# mano_rev_1_2_a.net
KiCad netlist of a schematic drawn in EAGLE
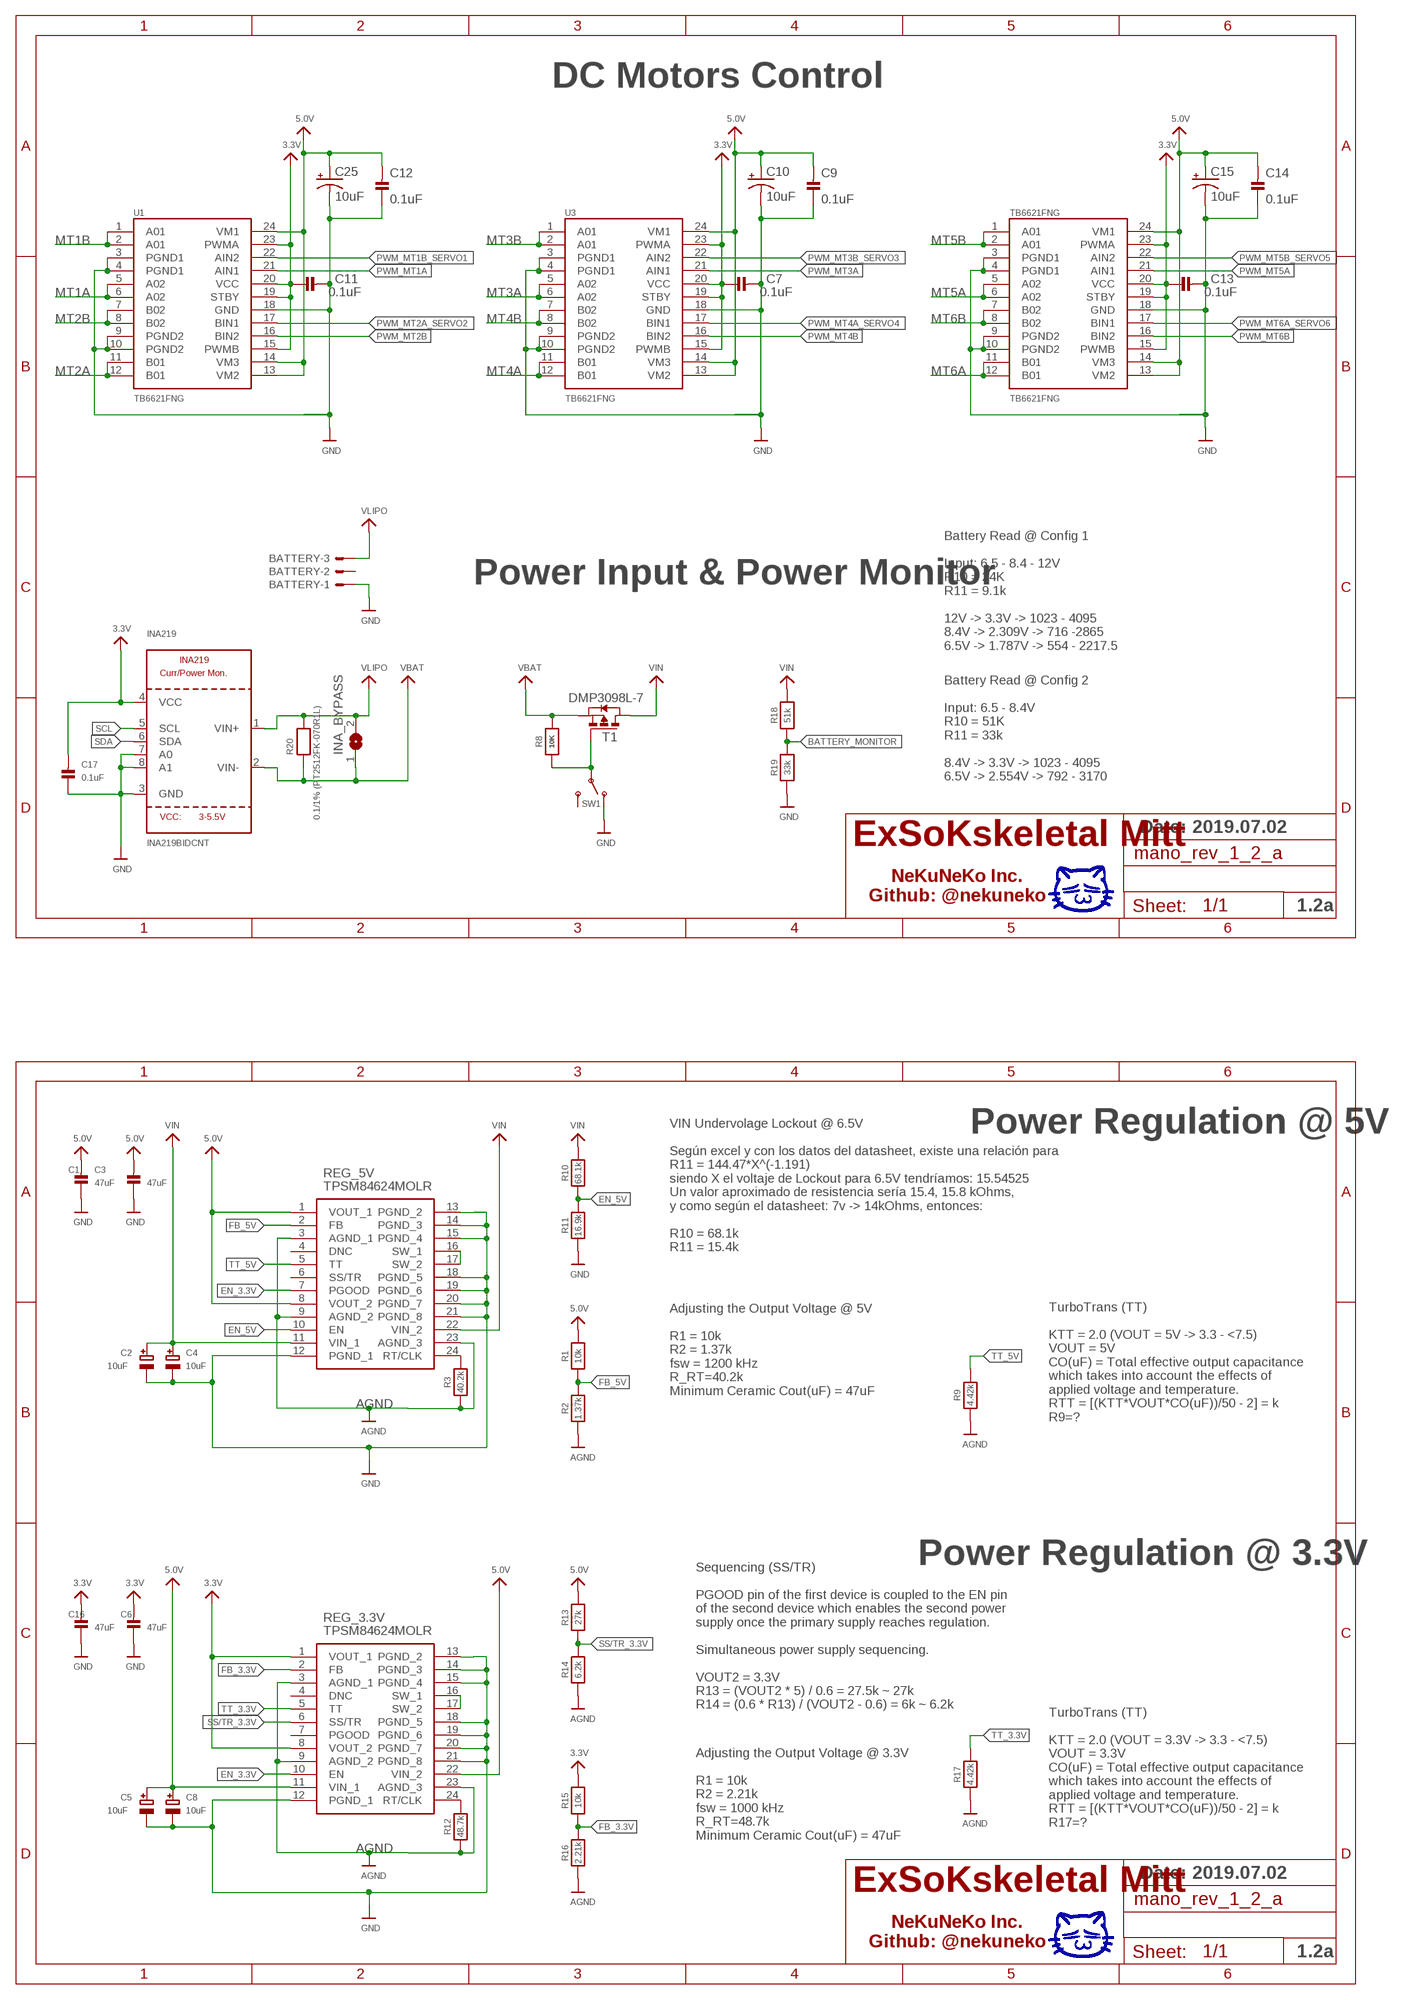
[diagram p0: schematic, sheet 1, part 1 of 2]
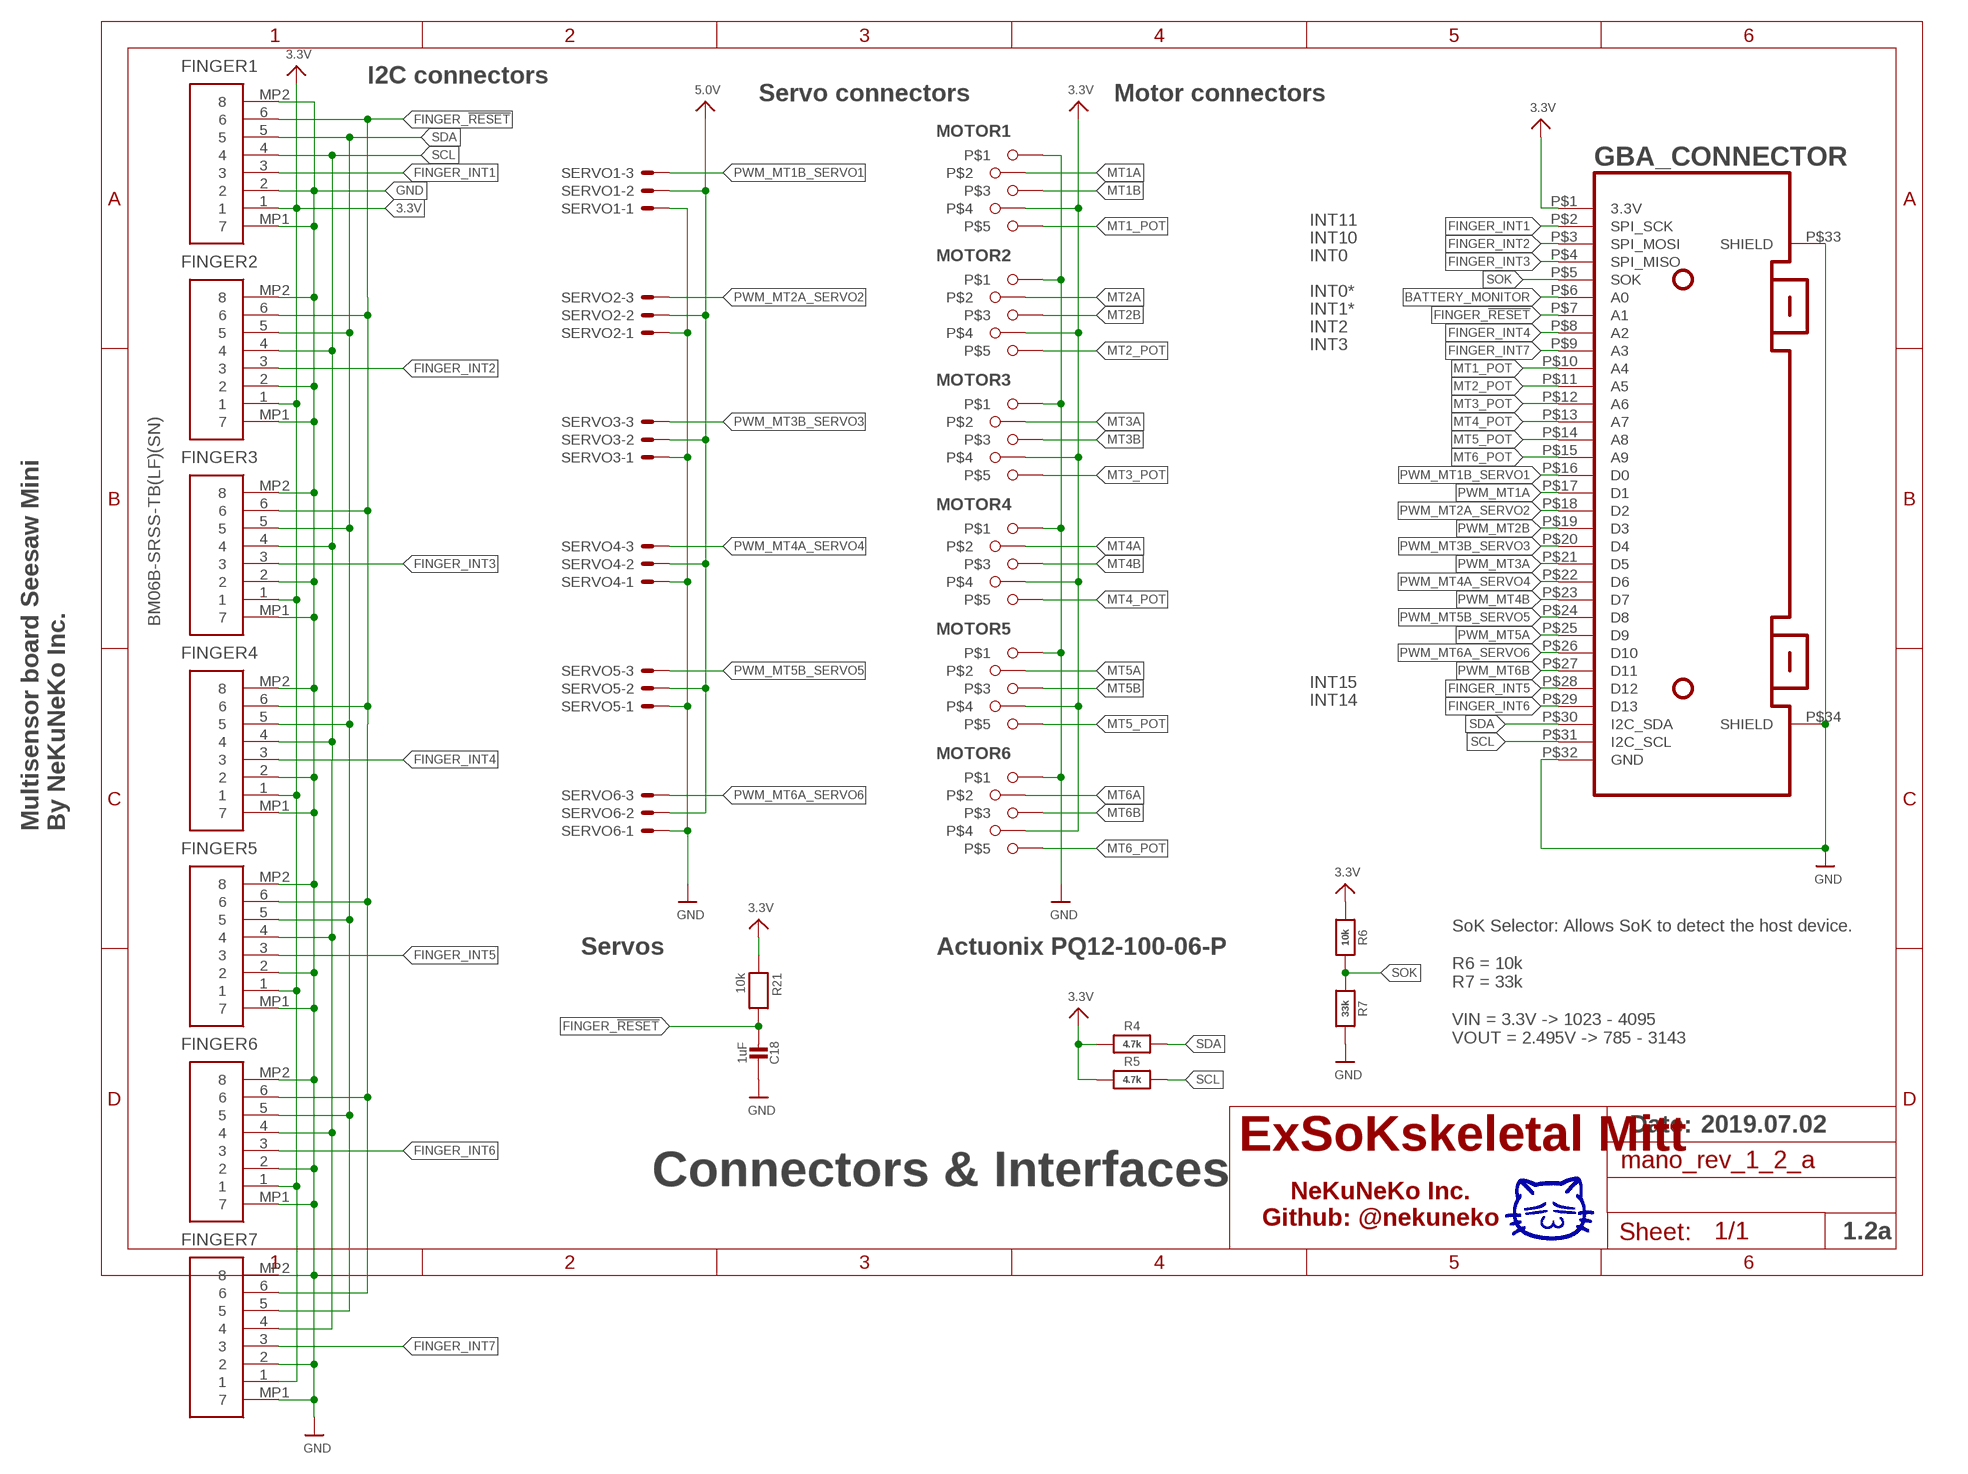
[diagram p1: schematic, sheet 1, part 2 of 2]

(export (version "E")
  (design (tool "Eeschema 10.0.6"))
  (components
    (comp (ref "BATTERY")
      (value "JST-XH-03-PIN-LONG-PAD")
      (footprint "eagle-import:JST-XH-03-PACKAGE-LONG-PAD")
      (libsource (lib "eagle-import") (part "JST-XH-03-PIN-LONG-PAD"))
    )
    (comp (ref "C1")
      (value "47uF")
      (footprint "eagle-import:_0603")
      (libsource (lib "eagle-import") (part "microbuilder_CAP_CERAMIC_0603"))
    )
    (comp (ref "C2")
      (value "10uF")
      (footprint "eagle-import:EIA3216-18_A-R")
      (libsource (lib "eagle-import") (part "CAP_TANTALUMA/3216_REFLOW"))
    )
    (comp (ref "C3")
      (value "47uF")
      (footprint "eagle-import:_0603")
      (libsource (lib "eagle-import") (part "microbuilder_CAP_CERAMIC_0603"))
    )
    (comp (ref "C4")
      (value "10uF")
      (footprint "eagle-import:EIA3216-18_A-R")
      (libsource (lib "eagle-import") (part "CAP_TANTALUMA/3216_REFLOW"))
    )
    (comp (ref "C5")
      (value "10uF")
      (footprint "eagle-import:EIA3216-18_A-R")
      (libsource (lib "eagle-import") (part "CAP_TANTALUMA/3216_REFLOW"))
    )
    (comp (ref "C6")
      (value "47uF")
      (footprint "eagle-import:_0603")
      (libsource (lib "eagle-import") (part "microbuilder_CAP_CERAMIC_0603"))
    )
    (comp (ref "C7")
      (value "0.1uF")
      (footprint "eagle-import:_0603")
      (libsource (lib "eagle-import") (part "microbuilder_CAP_CERAMIC_0603"))
    )
    (comp (ref "C8")
      (value "10uF")
      (footprint "eagle-import:EIA3216-18_A-R")
      (libsource (lib "eagle-import") (part "CAP_TANTALUMA/3216_REFLOW"))
    )
    (comp (ref "C9")
      (value "0.1uF")
      (footprint "eagle-import:_0603")
      (libsource (lib "eagle-import") (part "microbuilder_CAP_CERAMIC_0603"))
    )
    (comp (ref "C10")
      (value "10uF")
      (footprint "eagle-import:0603-POLAR")
      (fields (field (name "MPN") "F981A106MMA"))
      (libsource (lib "eagle-import") (part "10UF-POLAR-0603-6.3V-20%(TANT)"))
    )
    (comp (ref "C11")
      (value "0.1uF")
      (footprint "eagle-import:_0603")
      (libsource (lib "eagle-import") (part "microbuilder_CAP_CERAMIC_0603"))
    )
    (comp (ref "C12")
      (value "0.1uF")
      (footprint "eagle-import:_0603")
      (libsource (lib "eagle-import") (part "microbuilder_CAP_CERAMIC_0603"))
    )
    (comp (ref "C13")
      (value "0.1uF")
      (footprint "eagle-import:_0603")
      (libsource (lib "eagle-import") (part "microbuilder_CAP_CERAMIC_0603"))
    )
    (comp (ref "C14")
      (value "0.1uF")
      (footprint "eagle-import:_0603")
      (libsource (lib "eagle-import") (part "microbuilder_CAP_CERAMIC_0603"))
    )
    (comp (ref "C15")
      (value "10uF")
      (footprint "eagle-import:0603-POLAR")
      (fields (field (name "MPN") "F981A106MMA"))
      (libsource (lib "eagle-import") (part "10UF-POLAR-0603-6.3V-20%(TANT)"))
    )
    (comp (ref "C16")
      (value "47uF")
      (footprint "eagle-import:_0603")
      (libsource (lib "eagle-import") (part "microbuilder_CAP_CERAMIC_0603"))
    )
    (comp (ref "C17")
      (value "0.1uF")
      (footprint "eagle-import:_0603")
      (libsource (lib "eagle-import") (part "microbuilder_CAP_CERAMIC_0603"))
    )
    (comp (ref "C18")
      (value "1uF")
      (footprint "eagle-import:MICROBUILDER__0603")
      (libsource (lib "eagle-import") (part "CAP_CERAMIC_0603"))
    )
    (comp (ref "C25")
      (value "10uF")
      (footprint "eagle-import:0603-POLAR")
      (fields (field (name "MPN") "F981A106MMA"))
      (libsource (lib "eagle-import") (part "10UF-POLAR-0603-6.3V-20%(TANT)"))
    )
    (comp (ref "FINGER1")
      (value "BM06B-SRSS-TB(LF)(SN)")
      (footprint "eagle-import:BM06BSRSSTBLFSN")
      (fields (field (name "RS_PART_NUMBER") "5468782"))
      (libsource (lib "eagle-import") (part "BM06B-SRSS-TB(LF)(SN)"))
    )
    (comp (ref "FINGER2")
      (value "BM06B-SRSS-TB(LF)(SN)")
      (footprint "eagle-import:BM06BSRSSTBLFSN")
      (fields (field (name "RS_PART_NUMBER") "5468782"))
      (libsource (lib "eagle-import") (part "BM06B-SRSS-TB(LF)(SN)"))
    )
    (comp (ref "FINGER3")
      (value "BM06B-SRSS-TB(LF)(SN)")
      (footprint "eagle-import:BM06BSRSSTBLFSN")
      (fields (field (name "RS_PART_NUMBER") "5468782"))
      (libsource (lib "eagle-import") (part "BM06B-SRSS-TB(LF)(SN)"))
    )
    (comp (ref "FINGER4")
      (value "BM06B-SRSS-TB(LF)(SN)")
      (footprint "eagle-import:BM06BSRSSTBLFSN")
      (fields (field (name "RS_PART_NUMBER") "5468782"))
      (libsource (lib "eagle-import") (part "BM06B-SRSS-TB(LF)(SN)"))
    )
    (comp (ref "FINGER5")
      (value "BM06B-SRSS-TB(LF)(SN)")
      (footprint "eagle-import:BM06BSRSSTBLFSN")
      (fields (field (name "RS_PART_NUMBER") "5468782"))
      (libsource (lib "eagle-import") (part "BM06B-SRSS-TB(LF)(SN)"))
    )
    (comp (ref "FINGER6")
      (value "BM06B-SRSS-TB(LF)(SN)")
      (footprint "eagle-import:BM06BSRSSTBLFSN")
      (fields (field (name "RS_PART_NUMBER") "5468782"))
      (libsource (lib "eagle-import") (part "BM06B-SRSS-TB(LF)(SN)"))
    )
    (comp (ref "FINGER7")
      (value "BM06B-SRSS-TB(LF)(SN)")
      (footprint "eagle-import:BM06BSRSSTBLFSN")
      (fields (field (name "RS_PART_NUMBER") "5468782"))
      (libsource (lib "eagle-import") (part "BM06B-SRSS-TB(LF)(SN)"))
    )
    (comp (ref "GBA_CONNECTOR")
      (value "GBA_CARTRIDGEGBA_CARTRIDGE2")
      (footprint "eagle-import:GBA_CARTRIDGE2")
      (libsource (lib "eagle-import") (part "GBA_CARTRIDGEGBA_CARTRIDGE2"))
    )
    (comp (ref "INA219")
      (value "INA219BIDCNT")
      (footprint "eagle-import:SOT23-8")
      (libsource (lib "eagle-import") (part "INA219"))
    )
    (comp (ref "INA_BYPASS")
      (value "SOLDERJUMPERREFLOW_NOPASTE")
      (footprint "eagle-import:SOLDERJUMPER_REFLOW_NOPASTE")
      (libsource (lib "eagle-import") (part "SOLDERJUMPERREFLOW_NOPASTE"))
    )
    (comp (ref "MOTOR1")
      (value "Actuonix PQ12-100-06-P")
      (footprint "eagle-import:5PIN")
      (libsource (lib "eagle-import") (part "5PIN"))
    )
    (comp (ref "MOTOR2")
      (value "Actuonix PQ12-100-06-P")
      (footprint "eagle-import:5PIN")
      (libsource (lib "eagle-import") (part "5PIN"))
    )
    (comp (ref "MOTOR3")
      (value "Actuonix PQ12-100-06-P")
      (footprint "eagle-import:5PIN")
      (libsource (lib "eagle-import") (part "5PIN"))
    )
    (comp (ref "MOTOR4")
      (value "Actuonix PQ12-100-06-P")
      (footprint "eagle-import:5PIN")
      (libsource (lib "eagle-import") (part "5PIN"))
    )
    (comp (ref "MOTOR5")
      (value "Actuonix PQ12-100-06-P")
      (footprint "eagle-import:5PIN")
      (libsource (lib "eagle-import") (part "5PIN"))
    )
    (comp (ref "MOTOR6")
      (value "Actuonix PQ12-100-06-P")
      (footprint "eagle-import:5PIN")
      (libsource (lib "eagle-import") (part "5PIN"))
    )
    (comp (ref "R1")
      (value "10k")
      (footprint "eagle-import:_0603")
      (libsource (lib "eagle-import") (part "RESISTOR_0603"))
    )
    (comp (ref "R2")
      (value "1.37k")
      (footprint "eagle-import:_0603")
      (libsource (lib "eagle-import") (part "RESISTOR_0603"))
    )
    (comp (ref "R3")
      (value "40.2k")
      (footprint "eagle-import:_0603")
      (libsource (lib "eagle-import") (part "RESISTOR_0603"))
    )
    (comp (ref "R4")
      (value "4.7k")
      (footprint "eagle-import:_0603")
      (libsource (lib "eagle-import") (part "RESISTOR_0603"))
    )
    (comp (ref "R5")
      (value "4.7k")
      (footprint "eagle-import:_0603")
      (libsource (lib "eagle-import") (part "RESISTOR_0603"))
    )
    (comp (ref "R6")
      (value "10k")
      (footprint "eagle-import:_0603")
      (libsource (lib "eagle-import") (part "RESISTOR_0603"))
    )
    (comp (ref "R7")
      (value "33k")
      (footprint "eagle-import:_0603")
      (libsource (lib "eagle-import") (part "RESISTOR_0603"))
    )
    (comp (ref "R8")
      (value "10K")
      (footprint "eagle-import:_0805")
      (libsource (lib "eagle-import") (part "RESISTOR_0805"))
    )
    (comp (ref "R9")
      (value "4.42k")
      (footprint "eagle-import:_0603")
      (libsource (lib "eagle-import") (part "RESISTOR_0603"))
    )
    (comp (ref "R10")
      (value "68.1k")
      (footprint "eagle-import:_0603")
      (libsource (lib "eagle-import") (part "RESISTOR_0603"))
    )
    (comp (ref "R11")
      (value "16.9k")
      (footprint "eagle-import:_0603")
      (libsource (lib "eagle-import") (part "RESISTOR_0603"))
    )
    (comp (ref "R12")
      (value "48.7k")
      (footprint "eagle-import:_0603")
      (libsource (lib "eagle-import") (part "RESISTOR_0603"))
    )
    (comp (ref "R13")
      (value "27k")
      (footprint "eagle-import:_0603")
      (libsource (lib "eagle-import") (part "RESISTOR_0603"))
    )
    (comp (ref "R14")
      (value "6.2k")
      (footprint "eagle-import:_0603")
      (libsource (lib "eagle-import") (part "RESISTOR_0603"))
    )
    (comp (ref "R15")
      (value "10k")
      (footprint "eagle-import:_0603")
      (libsource (lib "eagle-import") (part "RESISTOR_0603"))
    )
    (comp (ref "R16")
      (value "2.21k")
      (footprint "eagle-import:_0603")
      (libsource (lib "eagle-import") (part "RESISTOR_0603"))
    )
    (comp (ref "R17")
      (value "4.42k")
      (footprint "eagle-import:_0603")
      (libsource (lib "eagle-import") (part "RESISTOR_0603"))
    )
    (comp (ref "R18")
      (value "51k")
      (footprint "eagle-import:_0603")
      (libsource (lib "eagle-import") (part "RESISTOR_0603"))
    )
    (comp (ref "R19")
      (value "33k")
      (footprint "eagle-import:_0603")
      (libsource (lib "eagle-import") (part "RESISTOR_0603"))
    )
    (comp (ref "R20")
      (value "0.1/1% (PT2512FK-070R1L)")
      (footprint "eagle-import:2512")
      (libsource (lib "eagle-import") (part "RESISTOR2512"))
    )
    (comp (ref "R21")
      (value "10k")
      (footprint "eagle-import:_0603")
      (libsource (lib "eagle-import") (part "RESISTOR_0603"))
    )
    (comp (ref "REG_3.3V")
      (value "TPSM84624MOLR")
      (footprint "eagle-import:TPSM84624MOLR")
      (fields (field (name "MOUSER_PART_NUMBER") "595-TPSM84624MOLR"))
      (libsource (lib "eagle-import") (part "TPSM84624MOLR"))
    )
    (comp (ref "REG_5V")
      (value "TPSM84624MOLR")
      (footprint "eagle-import:TPSM84624MOLR")
      (fields (field (name "MOUSER_PART_NUMBER") "595-TPSM84624MOLR"))
      (libsource (lib "eagle-import") (part "TPSM84624MOLR"))
    )
    (comp (ref "SERVO1")
      (value "JST-XH-03-PIN-LONG-PAD")
      (footprint "eagle-import:JST-XH-03-PACKAGE-LONG-PAD")
      (libsource (lib "eagle-import") (part "JST-XH-03-PIN-LONG-PAD"))
    )
    (comp (ref "SERVO2")
      (value "JST-XH-03-PIN-LONG-PAD")
      (footprint "eagle-import:JST-XH-03-PACKAGE-LONG-PAD")
      (libsource (lib "eagle-import") (part "JST-XH-03-PIN-LONG-PAD"))
    )
    (comp (ref "SERVO3")
      (value "JST-XH-03-PIN-LONG-PAD")
      (footprint "eagle-import:JST-XH-03-PACKAGE-LONG-PAD")
      (libsource (lib "eagle-import") (part "JST-XH-03-PIN-LONG-PAD"))
    )
    (comp (ref "SERVO4")
      (value "JST-XH-03-PIN-LONG-PAD")
      (footprint "eagle-import:JST-XH-03-PACKAGE-LONG-PAD")
      (libsource (lib "eagle-import") (part "JST-XH-03-PIN-LONG-PAD"))
    )
    (comp (ref "SERVO5")
      (value "JST-XH-03-PIN-LONG-PAD")
      (footprint "eagle-import:JST-XH-03-PACKAGE-LONG-PAD")
      (libsource (lib "eagle-import") (part "JST-XH-03-PIN-LONG-PAD"))
    )
    (comp (ref "SERVO6")
      (value "JST-XH-03-PIN-LONG-PAD")
      (footprint "eagle-import:JST-XH-03-PACKAGE-LONG-PAD")
      (libsource (lib "eagle-import") (part "JST-XH-03-PIN-LONG-PAD"))
    )
    (comp (ref "SW1")
      (value "SWITCH_SPDT")
      (footprint "eagle-import:SPDT_SMT_SSSS811101")
      (libsource (lib "eagle-import") (part "SWITCH_SPDT"))
    )
    (comp (ref "T1")
      (value "DMP3098L-7")
      (footprint "eagle-import:SOT-23")
      (libsource (lib "eagle-import") (part "PMOSSOT23"))
    )
    (comp (ref "TB6621FNG")
      (value "TB6621FNG")
      (footprint "eagle-import:SSOP24")
      (libsource (lib "eagle-import") (part "TB6621FNG"))
    )
    (comp (ref "U1")
      (value "TB6621FNG")
      (footprint "eagle-import:SSOP24")
      (libsource (lib "eagle-import") (part "TB6621FNG"))
    )
    (comp (ref "U3")
      (value "TB6621FNG")
      (footprint "eagle-import:SSOP24")
      (libsource (lib "eagle-import") (part "TB6621FNG"))
    )
  )
  (nets
    (net (code "1") (name "/FINGER_~{RESET}") (class "Default")
      (node (ref "C18") (pin "2") (pinfunction "2_2") (pintype "passive"))
      (node (ref "FINGER1") (pin "6") (pinfunction "6_6") (pintype "bidirectional"))
      (node (ref "FINGER2") (pin "6") (pinfunction "6_6") (pintype "bidirectional"))
      (node (ref "FINGER3") (pin "6") (pinfunction "6_6") (pintype "bidirectional"))
      (node (ref "FINGER4") (pin "6") (pinfunction "6_6") (pintype "bidirectional"))
      (node (ref "FINGER5") (pin "6") (pinfunction "6_6") (pintype "bidirectional"))
      (node (ref "FINGER6") (pin "6") (pinfunction "6_6") (pintype "bidirectional"))
      (node (ref "FINGER7") (pin "6") (pinfunction "6_6") (pintype "bidirectional"))
      (node (ref "GBA_CONNECTOR") (pin "P$7") (pinfunction "A1_P$7") (pintype "bidirectional"))
      (node (ref "R21") (pin "2") (pinfunction "2_2") (pintype "passive"))
    )
    (net (code "2") (name "3.3V") (class "Default")
      (node (ref "C11") (pin "1") (pinfunction "P$1_1") (pintype "passive"))
      (node (ref "C13") (pin "1") (pinfunction "P$1_1") (pintype "passive"))
      (node (ref "C16") (pin "2") (pinfunction "P$2_2") (pintype "passive"))
      (node (ref "C17") (pin "2") (pinfunction "P$2_2") (pintype "passive"))
      (node (ref "C6") (pin "2") (pinfunction "P$2_2") (pintype "passive"))
      (node (ref "C7") (pin "1") (pinfunction "P$1_1") (pintype "passive"))
      (node (ref "FINGER1") (pin "1") (pinfunction "1_1") (pintype "bidirectional"))
      (node (ref "FINGER2") (pin "1") (pinfunction "1_1") (pintype "bidirectional"))
      (node (ref "FINGER3") (pin "1") (pinfunction "1_1") (pintype "bidirectional"))
      (node (ref "FINGER4") (pin "1") (pinfunction "1_1") (pintype "bidirectional"))
      (node (ref "FINGER5") (pin "1") (pinfunction "1_1") (pintype "bidirectional"))
      (node (ref "FINGER6") (pin "1") (pinfunction "1_1") (pintype "bidirectional"))
      (node (ref "FINGER7") (pin "1") (pinfunction "1_1") (pintype "bidirectional"))
      (node (ref "GBA_CONNECTOR") (pin "P$1") (pinfunction "3.3V_P$1") (pintype "power_in"))
      (node (ref "INA219") (pin "4") (pinfunction "VCC_4") (pintype "bidirectional"))
      (node (ref "MOTOR1") (pin "4") (pinfunction "P$4_4") (pintype "bidirectional"))
      (node (ref "MOTOR2") (pin "4") (pinfunction "P$4_4") (pintype "bidirectional"))
      (node (ref "MOTOR3") (pin "4") (pinfunction "P$4_4") (pintype "bidirectional"))
      (node (ref "MOTOR4") (pin "4") (pinfunction "P$4_4") (pintype "bidirectional"))
      (node (ref "MOTOR5") (pin "4") (pinfunction "P$4_4") (pintype "bidirectional"))
      (node (ref "MOTOR6") (pin "4") (pinfunction "P$4_4") (pintype "bidirectional"))
      (node (ref "R15") (pin "2") (pinfunction "2_2") (pintype "passive"))
      (node (ref "R21") (pin "1") (pinfunction "1_1") (pintype "passive"))
      (node (ref "R4") (pin "1") (pinfunction "1_1") (pintype "passive"))
      (node (ref "R5") (pin "1") (pinfunction "1_1") (pintype "passive"))
      (node (ref "R6") (pin "1") (pinfunction "1_1") (pintype "passive"))
      (node (ref "REG_3.3V") (pin "1") (pinfunction "VOUT_1_1") (pintype "bidirectional"))
      (node (ref "REG_3.3V") (pin "8") (pinfunction "VOUT_2_8") (pintype "bidirectional"))
      (node (ref "TB6621FNG") (pin "15") (pinfunction "PWMB_15") (pintype "bidirectional"))
      (node (ref "TB6621FNG") (pin "19") (pinfunction "STBY_19") (pintype "bidirectional"))
      (node (ref "TB6621FNG") (pin "20") (pinfunction "VCC_20") (pintype "bidirectional"))
      (node (ref "TB6621FNG") (pin "23") (pinfunction "PWMA_23") (pintype "bidirectional"))
      (node (ref "U1") (pin "15") (pinfunction "PWMB_15") (pintype "bidirectional"))
      (node (ref "U1") (pin "19") (pinfunction "STBY_19") (pintype "bidirectional"))
      (node (ref "U1") (pin "20") (pinfunction "VCC_20") (pintype "bidirectional"))
      (node (ref "U1") (pin "23") (pinfunction "PWMA_23") (pintype "bidirectional"))
      (node (ref "U3") (pin "15") (pinfunction "PWMB_15") (pintype "bidirectional"))
      (node (ref "U3") (pin "19") (pinfunction "STBY_19") (pintype "bidirectional"))
      (node (ref "U3") (pin "20") (pinfunction "VCC_20") (pintype "bidirectional"))
      (node (ref "U3") (pin "23") (pinfunction "PWMA_23") (pintype "bidirectional"))
    )
    (net (code "3") (name "5.0V") (class "Default")
      (node (ref "C1") (pin "2") (pinfunction "P$2_2") (pintype "passive"))
      (node (ref "C10") (pin "+") (pinfunction "+_+") (pintype "passive"))
      (node (ref "C12") (pin "2") (pinfunction "P$2_2") (pintype "passive"))
      (node (ref "C14") (pin "2") (pinfunction "P$2_2") (pintype "passive"))
      (node (ref "C15") (pin "+") (pinfunction "+_+") (pintype "passive"))
      (node (ref "C25") (pin "+") (pinfunction "+_+") (pintype "passive"))
      (node (ref "C3") (pin "2") (pinfunction "P$2_2") (pintype "passive"))
      (node (ref "C5") (pin "+") (pinfunction "+_+") (pintype "passive"))
      (node (ref "C8") (pin "+") (pinfunction "+_+") (pintype "passive"))
      (node (ref "C9") (pin "2") (pinfunction "P$2_2") (pintype "passive"))
      (node (ref "R1") (pin "2") (pinfunction "2_2") (pintype "passive"))
      (node (ref "R13") (pin "2") (pinfunction "2_2") (pintype "passive"))
      (node (ref "REG_3.3V") (pin "11") (pinfunction "VIN_1_11") (pintype "bidirectional"))
      (node (ref "REG_3.3V") (pin "22") (pinfunction "VIN_2_22") (pintype "bidirectional"))
      (node (ref "REG_5V") (pin "1") (pinfunction "VOUT_1_1") (pintype "bidirectional"))
      (node (ref "REG_5V") (pin "8") (pinfunction "VOUT_2_8") (pintype "bidirectional"))
      (node (ref "SERVO1") (pin "2") (pinfunction "S_2") (pintype "passive"))
      (node (ref "SERVO2") (pin "2") (pinfunction "S_2") (pintype "passive"))
      (node (ref "SERVO3") (pin "2") (pinfunction "S_2") (pintype "passive"))
      (node (ref "SERVO4") (pin "2") (pinfunction "S_2") (pintype "passive"))
      (node (ref "SERVO5") (pin "2") (pinfunction "S_2") (pintype "passive"))
      (node (ref "SERVO6") (pin "2") (pinfunction "S_2") (pintype "passive"))
      (node (ref "TB6621FNG") (pin "13") (pinfunction "VM2_13") (pintype "bidirectional"))
      (node (ref "TB6621FNG") (pin "14") (pinfunction "VM3_14") (pintype "bidirectional"))
      (node (ref "TB6621FNG") (pin "24") (pinfunction "VM1_24") (pintype "bidirectional"))
      (node (ref "U1") (pin "13") (pinfunction "VM2_13") (pintype "bidirectional"))
      (node (ref "U1") (pin "14") (pinfunction "VM3_14") (pintype "bidirectional"))
      (node (ref "U1") (pin "24") (pinfunction "VM1_24") (pintype "bidirectional"))
      (node (ref "U3") (pin "13") (pinfunction "VM2_13") (pintype "bidirectional"))
      (node (ref "U3") (pin "14") (pinfunction "VM3_14") (pintype "bidirectional"))
      (node (ref "U3") (pin "24") (pinfunction "VM1_24") (pintype "bidirectional"))
    )
    (net (code "4") (name "AGND") (class "Default")
      (node (ref "R12") (pin "1") (pinfunction "1_1") (pintype "passive"))
      (node (ref "R14") (pin "1") (pinfunction "1_1") (pintype "passive"))
      (node (ref "R16") (pin "1") (pinfunction "1_1") (pintype "passive"))
      (node (ref "R17") (pin "1") (pinfunction "1_1") (pintype "passive"))
      (node (ref "R2") (pin "1") (pinfunction "1_1") (pintype "passive"))
      (node (ref "R3") (pin "1") (pinfunction "1_1") (pintype "passive"))
      (node (ref "R9") (pin "1") (pinfunction "1_1") (pintype "passive"))
      (node (ref "REG_3.3V") (pin "23") (pinfunction "AGND_3_23") (pintype "bidirectional"))
      (node (ref "REG_3.3V") (pin "3") (pinfunction "AGND_1_3") (pintype "bidirectional"))
      (node (ref "REG_3.3V") (pin "9") (pinfunction "AGND_2_9") (pintype "bidirectional"))
      (node (ref "REG_5V") (pin "23") (pinfunction "AGND_3_23") (pintype "bidirectional"))
      (node (ref "REG_5V") (pin "3") (pinfunction "AGND_1_3") (pintype "bidirectional"))
      (node (ref "REG_5V") (pin "9") (pinfunction "AGND_2_9") (pintype "bidirectional"))
    )
    (net (code "5") (name "BATTERY_MONITOR") (class "Default")
      (node (ref "GBA_CONNECTOR") (pin "P$6") (pinfunction "A0_P$6") (pintype "bidirectional"))
      (node (ref "R18") (pin "1") (pinfunction "1_1") (pintype "passive"))
      (node (ref "R19") (pin "2") (pinfunction "2_2") (pintype "passive"))
    )
    (net (code "6") (name "EN_3.3V") (class "Default")
      (node (ref "REG_3.3V") (pin "10") (pinfunction "EN_10") (pintype "bidirectional"))
      (node (ref "REG_5V") (pin "7") (pinfunction "PGOOD_7") (pintype "bidirectional"))
    )
    (net (code "7") (name "EN_5V") (class "Default")
      (node (ref "R10") (pin "1") (pinfunction "1_1") (pintype "passive"))
      (node (ref "R11") (pin "2") (pinfunction "2_2") (pintype "passive"))
      (node (ref "REG_5V") (pin "10") (pinfunction "EN_10") (pintype "bidirectional"))
    )
    (net (code "8") (name "FB_3.3V") (class "Default")
      (node (ref "R15") (pin "1") (pinfunction "1_1") (pintype "passive"))
      (node (ref "R16") (pin "2") (pinfunction "2_2") (pintype "passive"))
      (node (ref "REG_3.3V") (pin "2") (pinfunction "FB_2") (pintype "bidirectional"))
    )
    (net (code "9") (name "FB_5V") (class "Default")
      (node (ref "R1") (pin "1") (pinfunction "1_1") (pintype "passive"))
      (node (ref "R2") (pin "2") (pinfunction "2_2") (pintype "passive"))
      (node (ref "REG_5V") (pin "2") (pinfunction "FB_2") (pintype "bidirectional"))
    )
    (net (code "10") (name "FINGER_INT1") (class "Default")
      (node (ref "FINGER1") (pin "3") (pinfunction "3_3") (pintype "bidirectional"))
      (node (ref "GBA_CONNECTOR") (pin "P$2") (pinfunction "SPI_SCK_P$2") (pintype "bidirectional"))
    )
    (net (code "11") (name "FINGER_INT2") (class "Default")
      (node (ref "FINGER2") (pin "3") (pinfunction "3_3") (pintype "bidirectional"))
      (node (ref "GBA_CONNECTOR") (pin "P$3") (pinfunction "SPI_MOSI_P$3") (pintype "bidirectional"))
    )
    (net (code "12") (name "FINGER_INT3") (class "Default")
      (node (ref "FINGER3") (pin "3") (pinfunction "3_3") (pintype "bidirectional"))
      (node (ref "GBA_CONNECTOR") (pin "P$4") (pinfunction "SPI_MISO_P$4") (pintype "bidirectional"))
    )
    (net (code "13") (name "FINGER_INT4") (class "Default")
      (node (ref "FINGER4") (pin "3") (pinfunction "3_3") (pintype "bidirectional"))
      (node (ref "GBA_CONNECTOR") (pin "P$8") (pinfunction "A2_P$8") (pintype "bidirectional"))
    )
    (net (code "14") (name "FINGER_INT5") (class "Default")
      (node (ref "FINGER5") (pin "3") (pinfunction "3_3") (pintype "bidirectional"))
      (node (ref "GBA_CONNECTOR") (pin "P$28") (pinfunction "D12_P$28") (pintype "bidirectional"))
    )
    (net (code "15") (name "FINGER_INT6") (class "Default")
      (node (ref "FINGER6") (pin "3") (pinfunction "3_3") (pintype "bidirectional"))
      (node (ref "GBA_CONNECTOR") (pin "P$29") (pinfunction "D13_P$29") (pintype "bidirectional"))
    )
    (net (code "16") (name "FINGER_INT7") (class "Default")
      (node (ref "FINGER7") (pin "3") (pinfunction "3_3") (pintype "bidirectional"))
      (node (ref "GBA_CONNECTOR") (pin "P$9") (pinfunction "A3_P$9") (pintype "bidirectional"))
    )
    (net (code "17") (name "GND") (class "Default")
      (node (ref "BATTERY") (pin "1") (pinfunction "S_1") (pintype "passive"))
      (node (ref "C1") (pin "1") (pinfunction "P$1_1") (pintype "passive"))
      (node (ref "C10") (pin "-") (pinfunction "-_-") (pintype "passive"))
      (node (ref "C11") (pin "2") (pinfunction "P$2_2") (pintype "passive"))
      (node (ref "C12") (pin "1") (pinfunction "P$1_1") (pintype "passive"))
      (node (ref "C13") (pin "2") (pinfunction "P$2_2") (pintype "passive"))
      (node (ref "C14") (pin "1") (pinfunction "P$1_1") (pintype "passive"))
      (node (ref "C15") (pin "-") (pinfunction "-_-") (pintype "passive"))
      (node (ref "C16") (pin "1") (pinfunction "P$1_1") (pintype "passive"))
      (node (ref "C17") (pin "1") (pinfunction "P$1_1") (pintype "passive"))
      (node (ref "C18") (pin "1") (pinfunction "1_1") (pintype "passive"))
      (node (ref "C2") (pin "-") (pinfunction "-_-") (pintype "passive"))
      (node (ref "C25") (pin "-") (pinfunction "-_-") (pintype "passive"))
      (node (ref "C3") (pin "1") (pinfunction "P$1_1") (pintype "passive"))
      (node (ref "C4") (pin "-") (pinfunction "-_-") (pintype "passive"))
      (node (ref "C5") (pin "-") (pinfunction "-_-") (pintype "passive"))
      (node (ref "C6") (pin "1") (pinfunction "P$1_1") (pintype "passive"))
      (node (ref "C7") (pin "2") (pinfunction "P$2_2") (pintype "passive"))
      (node (ref "C8") (pin "-") (pinfunction "-_-") (pintype "passive"))
      (node (ref "C9") (pin "1") (pinfunction "P$1_1") (pintype "passive"))
      (node (ref "FINGER1") (pin "2") (pinfunction "2_2") (pintype "bidirectional"))
      (node (ref "FINGER1") (pin "MP1") (pinfunction "7_MP1") (pintype "bidirectional"))
      (node (ref "FINGER1") (pin "MP2") (pinfunction "8_MP2") (pintype "bidirectional"))
      (node (ref "FINGER2") (pin "2") (pinfunction "2_2") (pintype "bidirectional"))
      (node (ref "FINGER2") (pin "MP1") (pinfunction "7_MP1") (pintype "bidirectional"))
      (node (ref "FINGER2") (pin "MP2") (pinfunction "8_MP2") (pintype "bidirectional"))
      (node (ref "FINGER3") (pin "2") (pinfunction "2_2") (pintype "bidirectional"))
      (node (ref "FINGER3") (pin "MP1") (pinfunction "7_MP1") (pintype "bidirectional"))
      (node (ref "FINGER3") (pin "MP2") (pinfunction "8_MP2") (pintype "bidirectional"))
      (node (ref "FINGER4") (pin "2") (pinfunction "2_2") (pintype "bidirectional"))
      (node (ref "FINGER4") (pin "MP1") (pinfunction "7_MP1") (pintype "bidirectional"))
      (node (ref "FINGER4") (pin "MP2") (pinfunction "8_MP2") (pintype "bidirectional"))
      (node (ref "FINGER5") (pin "2") (pinfunction "2_2") (pintype "bidirectional"))
      (node (ref "FINGER5") (pin "MP1") (pinfunction "7_MP1") (pintype "bidirectional"))
      (node (ref "FINGER5") (pin "MP2") (pinfunction "8_MP2") (pintype "bidirectional"))
      (node (ref "FINGER6") (pin "2") (pinfunction "2_2") (pintype "bidirectional"))
      (node (ref "FINGER6") (pin "MP1") (pinfunction "7_MP1") (pintype "bidirectional"))
      (node (ref "FINGER6") (pin "MP2") (pinfunction "8_MP2") (pintype "bidirectional"))
      (node (ref "FINGER7") (pin "2") (pinfunction "2_2") (pintype "bidirectional"))
      (node (ref "FINGER7") (pin "MP1") (pinfunction "7_MP1") (pintype "bidirectional"))
      (node (ref "FINGER7") (pin "MP2") (pinfunction "8_MP2") (pintype "bidirectional"))
      (node (ref "GBA_CONNECTOR") (pin "P$32") (pinfunction "GND_P$32") (pintype "power_in"))
      (node (ref "GBA_CONNECTOR") (pin "P$33") (pinfunction "SHIELD_P$33") (pintype "bidirectional"))
      (node (ref "GBA_CONNECTOR") (pin "P$34") (pinfunction "SHIELD_P$34") (pintype "bidirectional"))
      (node (ref "INA219") (pin "3") (pinfunction "GND_3") (pintype "bidirectional"))
      (node (ref "INA219") (pin "7") (pinfunction "A0_7") (pintype "bidirectional"))
      (node (ref "INA219") (pin "8") (pinfunction "A1_8") (pintype "bidirectional"))
      (node (ref "MOTOR1") (pin "1") (pinfunction "P$1_1") (pintype "bidirectional"))
      (node (ref "MOTOR2") (pin "1") (pinfunction "P$1_1") (pintype "bidirectional"))
      (node (ref "MOTOR3") (pin "1") (pinfunction "P$1_1") (pintype "bidirectional"))
      (node (ref "MOTOR4") (pin "1") (pinfunction "P$1_1") (pintype "bidirectional"))
      (node (ref "MOTOR5") (pin "1") (pinfunction "P$1_1") (pintype "bidirectional"))
      (node (ref "MOTOR6") (pin "1") (pinfunction "P$1_1") (pintype "bidirectional"))
      (node (ref "R11") (pin "1") (pinfunction "1_1") (pintype "passive"))
      (node (ref "R19") (pin "1") (pinfunction "1_1") (pintype "passive"))
      (node (ref "R7") (pin "2") (pinfunction "2_2") (pintype "passive"))
      (node (ref "REG_3.3V") (pin "12") (pinfunction "PGND_1_12") (pintype "bidirectional"))
      (node (ref "REG_3.3V") (pin "13") (pinfunction "PGND_2_13") (pintype "bidirectional"))
      (node (ref "REG_3.3V") (pin "14") (pinfunction "PGND_3_14") (pintype "bidirectional"))
      (node (ref "REG_3.3V") (pin "15") (pinfunction "PGND_4_15") (pintype "bidirectional"))
      (node (ref "REG_3.3V") (pin "18") (pinfunction "PGND_5_18") (pintype "bidirectional"))
      (node (ref "REG_3.3V") (pin "19") (pinfunction "PGND_6_19") (pintype "bidirectional"))
      (node (ref "REG_3.3V") (pin "20") (pinfunction "PGND_7_20") (pintype "bidirectional"))
      (node (ref "REG_3.3V") (pin "21") (pinfunction "PGND_8_21") (pintype "bidirectional"))
      (node (ref "REG_5V") (pin "12") (pinfunction "PGND_1_12") (pintype "bidirectional"))
      (node (ref "REG_5V") (pin "13") (pinfunction "PGND_2_13") (pintype "bidirectional"))
      (node (ref "REG_5V") (pin "14") (pinfunction "PGND_3_14") (pintype "bidirectional"))
      (node (ref "REG_5V") (pin "15") (pinfunction "PGND_4_15") (pintype "bidirectional"))
      (node (ref "REG_5V") (pin "18") (pinfunction "PGND_5_18") (pintype "bidirectional"))
      (node (ref "REG_5V") (pin "19") (pinfunction "PGND_6_19") (pintype "bidirectional"))
      (node (ref "REG_5V") (pin "20") (pinfunction "PGND_7_20") (pintype "bidirectional"))
      (node (ref "REG_5V") (pin "21") (pinfunction "PGND_8_21") (pintype "bidirectional"))
      (node (ref "SERVO1") (pin "1") (pinfunction "S_1") (pintype "passive"))
      (node (ref "SERVO2") (pin "1") (pinfunction "S_1") (pintype "passive"))
      (node (ref "SERVO3") (pin "1") (pinfunction "S_1") (pintype "passive"))
      (node (ref "SERVO4") (pin "1") (pinfunction "S_1") (pintype "passive"))
      (node (ref "SERVO5") (pin "1") (pinfunction "S_1") (pintype "passive"))
      (node (ref "SERVO6") (pin "1") (pinfunction "S_1") (pintype "passive"))
      (node (ref "SW1") (pin "A") (pinfunction "O_A") (pintype "passive"))
      (node (ref "TB6621FNG") (pin "10") (pinfunction "PGND2_10") (pintype "bidirectional"))
      (node (ref "TB6621FNG") (pin "18") (pinfunction "GND_18") (pintype "bidirectional"))
      (node (ref "TB6621FNG") (pin "3") (pinfunction "PGND1_3") (pintype "bidirectional"))
      (node (ref "TB6621FNG") (pin "4") (pinfunction "PGND1_4") (pintype "bidirectional"))
      (node (ref "TB6621FNG") (pin "9") (pinfunction "PGND2_9") (pintype "bidirectional"))
      (node (ref "U1") (pin "10") (pinfunction "PGND2_10") (pintype "bidirectional"))
      (node (ref "U1") (pin "18") (pinfunction "GND_18") (pintype "bidirectional"))
      (node (ref "U1") (pin "3") (pinfunction "PGND1_3") (pintype "bidirectional"))
      (node (ref "U1") (pin "4") (pinfunction "PGND1_4") (pintype "bidirectional"))
      (node (ref "U1") (pin "9") (pinfunction "PGND2_9") (pintype "bidirectional"))
      (node (ref "U3") (pin "10") (pinfunction "PGND2_10") (pintype "bidirectional"))
      (node (ref "U3") (pin "18") (pinfunction "GND_18") (pintype "bidirectional"))
      (node (ref "U3") (pin "3") (pinfunction "PGND1_3") (pintype "bidirectional"))
      (node (ref "U3") (pin "4") (pinfunction "PGND1_4") (pintype "bidirectional"))
      (node (ref "U3") (pin "9") (pinfunction "PGND2_9") (pintype "bidirectional"))
    )
    (net (code "18") (name "MT1A") (class "Default")
      (node (ref "MOTOR1") (pin "2") (pinfunction "P$2_2") (pintype "bidirectional"))
      (node (ref "U1") (pin "5") (pinfunction "A02_5") (pintype "bidirectional"))
      (node (ref "U1") (pin "6") (pinfunction "A02_6") (pintype "bidirectional"))
    )
    (net (code "19") (name "MT1B") (class "Default")
      (node (ref "MOTOR1") (pin "3") (pinfunction "P$3_3") (pintype "bidirectional"))
      (node (ref "U1") (pin "1") (pinfunction "A01_1") (pintype "bidirectional"))
      (node (ref "U1") (pin "2") (pinfunction "A01_2") (pintype "bidirectional"))
    )
    (net (code "20") (name "MT1_POT") (class "Default")
      (node (ref "GBA_CONNECTOR") (pin "P$10") (pinfunction "A4_P$10") (pintype "bidirectional"))
      (node (ref "MOTOR1") (pin "5") (pinfunction "P$5_5") (pintype "bidirectional"))
    )
    (net (code "21") (name "MT2A") (class "Default")
      (node (ref "MOTOR2") (pin "2") (pinfunction "P$2_2") (pintype "bidirectional"))
      (node (ref "U1") (pin "11") (pinfunction "B01_11") (pintype "bidirectional"))
      (node (ref "U1") (pin "12") (pinfunction "B01_12") (pintype "bidirectional"))
    )
    (net (code "22") (name "MT2B") (class "Default")
      (node (ref "MOTOR2") (pin "3") (pinfunction "P$3_3") (pintype "bidirectional"))
      (node (ref "U1") (pin "7") (pinfunction "B02_7") (pintype "bidirectional"))
      (node (ref "U1") (pin "8") (pinfunction "B02_8") (pintype "bidirectional"))
    )
    (net (code "23") (name "MT2_POT") (class "Default")
      (node (ref "GBA_CONNECTOR") (pin "P$11") (pinfunction "A5_P$11") (pintype "bidirectional"))
      (node (ref "MOTOR2") (pin "5") (pinfunction "P$5_5") (pintype "bidirectional"))
    )
    (net (code "24") (name "MT3A") (class "Default")
      (node (ref "MOTOR3") (pin "2") (pinfunction "P$2_2") (pintype "bidirectional"))
      (node (ref "U3") (pin "5") (pinfunction "A02_5") (pintype "bidirectional"))
      (node (ref "U3") (pin "6") (pinfunction "A02_6") (pintype "bidirectional"))
    )
    (net (code "25") (name "MT3B") (class "Default")
      (node (ref "MOTOR3") (pin "3") (pinfunction "P$3_3") (pintype "bidirectional"))
      (node (ref "U3") (pin "1") (pinfunction "A01_1") (pintype "bidirectional"))
      (node (ref "U3") (pin "2") (pinfunction "A01_2") (pintype "bidirectional"))
    )
    (net (code "26") (name "MT3_POT") (class "Default")
      (node (ref "GBA_CONNECTOR") (pin "P$12") (pinfunction "A6_P$12") (pintype "bidirectional"))
      (node (ref "MOTOR3") (pin "5") (pinfunction "P$5_5") (pintype "bidirectional"))
    )
    (net (code "27") (name "MT4A") (class "Default")
      (node (ref "MOTOR4") (pin "2") (pinfunction "P$2_2") (pintype "bidirectional"))
      (node (ref "U3") (pin "11") (pinfunction "B01_11") (pintype "bidirectional"))
      (node (ref "U3") (pin "12") (pinfunction "B01_12") (pintype "bidirectional"))
    )
    (net (code "28") (name "MT4B") (class "Default")
      (node (ref "MOTOR4") (pin "3") (pinfunction "P$3_3") (pintype "bidirectional"))
      (node (ref "U3") (pin "7") (pinfunction "B02_7") (pintype "bidirectional"))
      (node (ref "U3") (pin "8") (pinfunction "B02_8") (pintype "bidirectional"))
    )
    (net (code "29") (name "MT4_POT") (class "Default")
      (node (ref "GBA_CONNECTOR") (pin "P$13") (pinfunction "A7_P$13") (pintype "bidirectional"))
      (node (ref "MOTOR4") (pin "5") (pinfunction "P$5_5") (pintype "bidirectional"))
    )
    (net (code "30") (name "MT5A") (class "Default")
      (node (ref "MOTOR5") (pin "2") (pinfunction "P$2_2") (pintype "bidirectional"))
      (node (ref "TB6621FNG") (pin "5") (pinfunction "A02_5") (pintype "bidirectional"))
      (node (ref "TB6621FNG") (pin "6") (pinfunction "A02_6") (pintype "bidirectional"))
    )
    (net (code "31") (name "MT5B") (class "Default")
      (node (ref "MOTOR5") (pin "3") (pinfunction "P$3_3") (pintype "bidirectional"))
      (node (ref "TB6621FNG") (pin "1") (pinfunction "A01_1") (pintype "bidirectional"))
      (node (ref "TB6621FNG") (pin "2") (pinfunction "A01_2") (pintype "bidirectional"))
    )
    (net (code "32") (name "MT5_POT") (class "Default")
      (node (ref "GBA_CONNECTOR") (pin "P$14") (pinfunction "A8_P$14") (pintype "bidirectional"))
      (node (ref "MOTOR5") (pin "5") (pinfunction "P$5_5") (pintype "bidirectional"))
    )
    (net (code "33") (name "MT6A") (class "Default")
      (node (ref "MOTOR6") (pin "2") (pinfunction "P$2_2") (pintype "bidirectional"))
      (node (ref "TB6621FNG") (pin "11") (pinfunction "B01_11") (pintype "bidirectional"))
      (node (ref "TB6621FNG") (pin "12") (pinfunction "B01_12") (pintype "bidirectional"))
    )
    (net (code "34") (name "MT6B") (class "Default")
      (node (ref "MOTOR6") (pin "3") (pinfunction "P$3_3") (pintype "bidirectional"))
      (node (ref "TB6621FNG") (pin "7") (pinfunction "B02_7") (pintype "bidirectional"))
      (node (ref "TB6621FNG") (pin "8") (pinfunction "B02_8") (pintype "bidirectional"))
    )
    (net (code "35") (name "MT6_POT") (class "Default")
      (node (ref "GBA_CONNECTOR") (pin "P$15") (pinfunction "A9_P$15") (pintype "bidirectional"))
      (node (ref "MOTOR6") (pin "5") (pinfunction "P$5_5") (pintype "bidirectional"))
    )
    (net (code "36") (name "Net-(REG_3.3V-RT{slash}CLK)") (class "Default")
      (node (ref "R12") (pin "2") (pinfunction "2_2") (pintype "passive"))
      (node (ref "REG_3.3V") (pin "24") (pinfunction "RT/CLK_24") (pintype "bidirectional"))
    )
    (net (code "37") (name "Net-(REG_3.3V-SW_1)") (class "Default")
      (node (ref "REG_3.3V") (pin "16") (pinfunction "SW_1_16") (pintype "bidirectional"))
      (node (ref "REG_3.3V") (pin "17") (pinfunction "SW_2_17") (pintype "bidirectional"))
    )
    (net (code "38") (name "Net-(REG_5V-RT{slash}CLK)") (class "Default")
      (node (ref "R3") (pin "2") (pinfunction "2_2") (pintype "passive"))
      (node (ref "REG_5V") (pin "24") (pinfunction "RT/CLK_24") (pintype "bidirectional"))
    )
    (net (code "39") (name "Net-(REG_5V-SW_1)") (class "Default")
      (node (ref "REG_5V") (pin "16") (pinfunction "SW_1_16") (pintype "bidirectional"))
      (node (ref "REG_5V") (pin "17") (pinfunction "SW_2_17") (pintype "bidirectional"))
    )
    (net (code "40") (name "Net-(SW1-P)") (class "Default")
      (node (ref "R8") (pin "1") (pinfunction "1_1") (pintype "passive"))
      (node (ref "SW1") (pin "B") (pinfunction "P_B") (pintype "passive"))
      (node (ref "T1") (pin "3") (pinfunction "G_3") (pintype "passive"))
    )
    (net (code "41") (name "PWM_MT1A") (class "Default")
      (node (ref "GBA_CONNECTOR") (pin "P$17") (pinfunction "D1_P$17") (pintype "bidirectional"))
      (node (ref "U1") (pin "21") (pinfunction "AIN1_21") (pintype "bidirectional"))
    )
    (net (code "42") (name "PWM_MT1B_SERVO1") (class "Default")
      (node (ref "GBA_CONNECTOR") (pin "P$16") (pinfunction "D0_P$16") (pintype "bidirectional"))
      (node (ref "SERVO1") (pin "3") (pinfunction "S_3") (pintype "passive"))
      (node (ref "U1") (pin "22") (pinfunction "AIN2_22") (pintype "bidirectional"))
    )
    (net (code "43") (name "PWM_MT2A_SERVO2") (class "Default")
      (node (ref "GBA_CONNECTOR") (pin "P$18") (pinfunction "D2_P$18") (pintype "bidirectional"))
      (node (ref "SERVO2") (pin "3") (pinfunction "S_3") (pintype "passive"))
      (node (ref "U1") (pin "17") (pinfunction "BIN1_17") (pintype "bidirectional"))
    )
    (net (code "44") (name "PWM_MT2B") (class "Default")
      (node (ref "GBA_CONNECTOR") (pin "P$19") (pinfunction "D3_P$19") (pintype "bidirectional"))
      (node (ref "U1") (pin "16") (pinfunction "BIN2_16") (pintype "bidirectional"))
    )
    (net (code "45") (name "PWM_MT3A") (class "Default")
      (node (ref "GBA_CONNECTOR") (pin "P$21") (pinfunction "D5_P$21") (pintype "bidirectional"))
      (node (ref "U3") (pin "21") (pinfunction "AIN1_21") (pintype "bidirectional"))
    )
    (net (code "46") (name "PWM_MT3B_SERVO3") (class "Default")
      (node (ref "GBA_CONNECTOR") (pin "P$20") (pinfunction "D4_P$20") (pintype "bidirectional"))
      (node (ref "SERVO3") (pin "3") (pinfunction "S_3") (pintype "passive"))
      (node (ref "U3") (pin "22") (pinfunction "AIN2_22") (pintype "bidirectional"))
    )
    (net (code "47") (name "PWM_MT4A_SERVO4") (class "Default")
      (node (ref "GBA_CONNECTOR") (pin "P$22") (pinfunction "D6_P$22") (pintype "bidirectional"))
      (node (ref "SERVO4") (pin "3") (pinfunction "S_3") (pintype "passive"))
      (node (ref "U3") (pin "17") (pinfunction "BIN1_17") (pintype "bidirectional"))
    )
    (net (code "48") (name "PWM_MT4B") (class "Default")
      (node (ref "GBA_CONNECTOR") (pin "P$23") (pinfunction "D7_P$23") (pintype "bidirectional"))
      (node (ref "U3") (pin "16") (pinfunction "BIN2_16") (pintype "bidirectional"))
    )
    (net (code "49") (name "PWM_MT5A") (class "Default")
      (node (ref "GBA_CONNECTOR") (pin "P$25") (pinfunction "D9_P$25") (pintype "bidirectional"))
      (node (ref "TB6621FNG") (pin "21") (pinfunction "AIN1_21") (pintype "bidirectional"))
    )
    (net (code "50") (name "PWM_MT5B_SERVO5") (class "Default")
      (node (ref "GBA_CONNECTOR") (pin "P$24") (pinfunction "D8_P$24") (pintype "bidirectional"))
      (node (ref "SERVO5") (pin "3") (pinfunction "S_3") (pintype "passive"))
      (node (ref "TB6621FNG") (pin "22") (pinfunction "AIN2_22") (pintype "bidirectional"))
    )
    (net (code "51") (name "PWM_MT6A_SERVO6") (class "Default")
      (node (ref "GBA_CONNECTOR") (pin "P$26") (pinfunction "D10_P$26") (pintype "bidirectional"))
      (node (ref "SERVO6") (pin "3") (pinfunction "S_3") (pintype "passive"))
      (node (ref "TB6621FNG") (pin "17") (pinfunction "BIN1_17") (pintype "bidirectional"))
    )
    (net (code "52") (name "PWM_MT6B") (class "Default")
      (node (ref "GBA_CONNECTOR") (pin "P$27") (pinfunction "D11_P$27") (pintype "bidirectional"))
      (node (ref "TB6621FNG") (pin "16") (pinfunction "BIN2_16") (pintype "bidirectional"))
    )
    (net (code "53") (name "SCL") (class "Default")
      (node (ref "FINGER1") (pin "4") (pinfunction "4_4") (pintype "bidirectional"))
      (node (ref "FINGER2") (pin "4") (pinfunction "4_4") (pintype "bidirectional"))
      (node (ref "FINGER3") (pin "4") (pinfunction "4_4") (pintype "bidirectional"))
      (node (ref "FINGER4") (pin "4") (pinfunction "4_4") (pintype "bidirectional"))
      (node (ref "FINGER5") (pin "4") (pinfunction "4_4") (pintype "bidirectional"))
      (node (ref "FINGER6") (pin "4") (pinfunction "4_4") (pintype "bidirectional"))
      (node (ref "FINGER7") (pin "4") (pinfunction "4_4") (pintype "bidirectional"))
      (node (ref "GBA_CONNECTOR") (pin "P$31") (pinfunction "I2C_SCL_P$31") (pintype "bidirectional"))
      (node (ref "INA219") (pin "5") (pinfunction "SCL_5") (pintype "bidirectional"))
      (node (ref "R5") (pin "2") (pinfunction "2_2") (pintype "passive"))
    )
    (net (code "54") (name "SDA") (class "Default")
      (node (ref "FINGER1") (pin "5") (pinfunction "5_5") (pintype "bidirectional"))
      (node (ref "FINGER2") (pin "5") (pinfunction "5_5") (pintype "bidirectional"))
      (node (ref "FINGER3") (pin "5") (pinfunction "5_5") (pintype "bidirectional"))
      (node (ref "FINGER4") (pin "5") (pinfunction "5_5") (pintype "bidirectional"))
      (node (ref "FINGER5") (pin "5") (pinfunction "5_5") (pintype "bidirectional"))
      (node (ref "FINGER6") (pin "5") (pinfunction "5_5") (pintype "bidirectional"))
      (node (ref "FINGER7") (pin "5") (pinfunction "5_5") (pintype "bidirectional"))
      (node (ref "GBA_CONNECTOR") (pin "P$30") (pinfunction "I2C_SDA_P$30") (pintype "bidirectional"))
      (node (ref "INA219") (pin "6") (pinfunction "SDA_6") (pintype "bidirectional"))
      (node (ref "R4") (pin "2") (pinfunction "2_2") (pintype "passive"))
    )
    (net (code "55") (name "SOK") (class "Default")
      (node (ref "GBA_CONNECTOR") (pin "P$5") (pinfunction "SOK_P$5") (pintype "bidirectional"))
      (node (ref "R6") (pin "2") (pinfunction "2_2") (pintype "passive"))
      (node (ref "R7") (pin "1") (pinfunction "1_1") (pintype "passive"))
    )
    (net (code "56") (name "SS{slash}TR_3.3V") (class "Default")
      (node (ref "R13") (pin "1") (pinfunction "1_1") (pintype "passive"))
      (node (ref "R14") (pin "2") (pinfunction "2_2") (pintype "passive"))
      (node (ref "REG_3.3V") (pin "6") (pinfunction "SS/TR_6") (pintype "bidirectional"))
    )
    (net (code "57") (name "TT_3.3V") (class "Default")
      (node (ref "R17") (pin "2") (pinfunction "2_2") (pintype "passive"))
      (node (ref "REG_3.3V") (pin "5") (pinfunction "TT_5") (pintype "bidirectional"))
    )
    (net (code "58") (name "TT_5V") (class "Default")
      (node (ref "R9") (pin "2") (pinfunction "2_2") (pintype "passive"))
      (node (ref "REG_5V") (pin "5") (pinfunction "TT_5") (pintype "bidirectional"))
    )
    (net (code "59") (name "VBAT") (class "Default")
      (node (ref "INA219") (pin "2") (pinfunction "VIN-_2") (pintype "bidirectional"))
      (node (ref "INA_BYPASS") (pin "1") (pinfunction "1_1") (pintype "passive"))
      (node (ref "R20") (pin "1") (pinfunction "1_1") (pintype "passive"))
      (node (ref "R8") (pin "2") (pinfunction "2_2") (pintype "passive"))
      (node (ref "T1") (pin "2") (pinfunction "S_2") (pintype "passive"))
    )
    (net (code "60") (name "VIN") (class "Default")
      (node (ref "C2") (pin "+") (pinfunction "+_+") (pintype "passive"))
      (node (ref "C4") (pin "+") (pinfunction "+_+") (pintype "passive"))
      (node (ref "R10") (pin "2") (pinfunction "2_2") (pintype "passive"))
      (node (ref "R18") (pin "2") (pinfunction "2_2") (pintype "passive"))
      (node (ref "REG_5V") (pin "11") (pinfunction "VIN_1_11") (pintype "bidirectional"))
      (node (ref "REG_5V") (pin "22") (pinfunction "VIN_2_22") (pintype "bidirectional"))
      (node (ref "T1") (pin "1") (pinfunction "D_1") (pintype "passive"))
    )
    (net (code "61") (name "VLIPO") (class "Default")
      (node (ref "BATTERY") (pin "3") (pinfunction "S_3") (pintype "passive"))
      (node (ref "INA219") (pin "1") (pinfunction "VIN+_1") (pintype "bidirectional"))
      (node (ref "INA_BYPASS") (pin "2") (pinfunction "2_2") (pintype "passive"))
      (node (ref "R20") (pin "2") (pinfunction "2_2") (pintype "passive"))
    )
    (net (code "62") (name "unconnected-(BATTERYB-S-Pad2)") (class "Default")
      (node (ref "BATTERY") (pin "2") (pinfunction "S_2") (pintype "passive"))
    )
    (net (code "63") (name "unconnected-(REG_3.3V-DNC-Pad4)") (class "Default")
      (node (ref "REG_3.3V") (pin "4") (pinfunction "DNC_4") (pintype "bidirectional"))
    )
    (net (code "64") (name "unconnected-(REG_3.3V-PGOOD-Pad7)") (class "Default")
      (node (ref "REG_3.3V") (pin "7") (pinfunction "PGOOD_7") (pintype "bidirectional"))
    )
    (net (code "65") (name "unconnected-(REG_5V-DNC-Pad4)") (class "Default")
      (node (ref "REG_5V") (pin "4") (pinfunction "DNC_4") (pintype "bidirectional"))
    )
    (net (code "66") (name "unconnected-(REG_5V-SS{slash}TR-Pad6)") (class "Default")
      (node (ref "REG_5V") (pin "6") (pinfunction "SS/TR_6") (pintype "bidirectional"))
    )
    (net (code "67") (name "unconnected-(SW1-S-PadC)") (class "Default")
      (node (ref "SW1") (pin "C") (pinfunction "S_C") (pintype "passive"))
    )
  )
)
